# BUCK_5v_TPS54340_P-MOS.net
KiCad netlist of a schematic drawn in Altium Designer
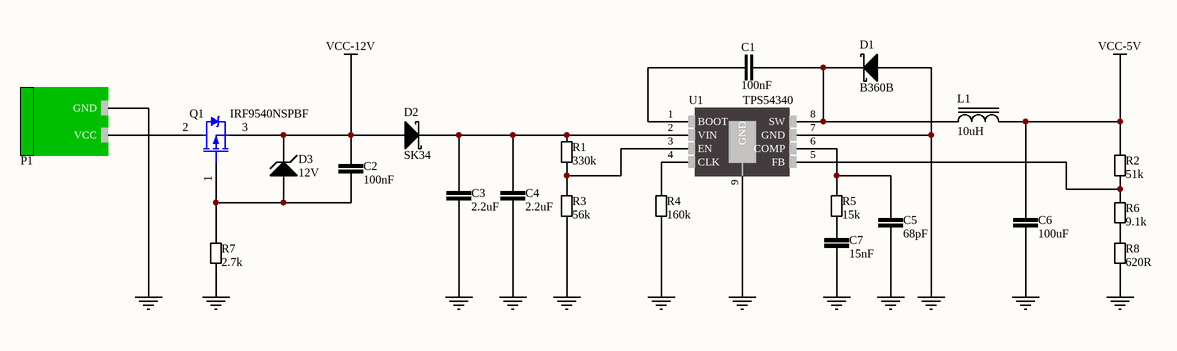
[diagram p0: BUCK_5v_TPS54340_P-MOS.SchDoc]

(export (version "E")
  (design (tool "Eeschema 10.0.6"))
  (components
    (comp (ref "C1")
      (value "100nF")
      (footprint "CER_0805")
      (description "CAP CER 100n 50V X7R 10% 0805")
      (libsource (lib "Capacitors") (part "00002105"))
    )
    (comp (ref "C2")
      (value "100nF")
      (footprint "CER_0805")
      (description "CAP CER 100n 50V X7R 10% 0805")
      (libsource (lib "Capacitors") (part "00002105"))
    )
    (comp (ref "C3")
      (value "2.2uF")
      (footprint "CER_1210")
      (description "CAP CER 2.2u")
      (libsource (lib "Capacitors") (part "00001225"))
    )
    (comp (ref "C4")
      (value "2.2uF")
      (footprint "CER_1210")
      (description "CAP CER 2.2u")
      (libsource (lib "Capacitors") (part "00001225"))
    )
    (comp (ref "C5")
      (value "68pF")
      (footprint "CER_0805")
      (description "CAP CER 100n 50V X7R 10% 0805")
      (libsource (lib "Capacitors") (part "00002105"))
    )
    (comp (ref "C6")
      (value "100uF")
      (footprint "CER_1210")
      (description "CAP CER 100u X5R 6.3V 10% 1210")
      (libsource (lib "Capacitors") (part "00002108"))
    )
    (comp (ref "C7")
      (value "15nF")
      (footprint "CER_0805")
      (description "CAP CER 100n 50V X7R 10% 0805")
      (libsource (lib "Capacitors") (part "00002105"))
    )
    (comp (ref "D1")
      (value "B360B")
      (footprint "DO214AC")
      (description "DIODE SCHOTTKY 60V 3A DO214AC")
      (fields (field (name "MANUFACTURER") "Vishay Semiconductor Diodes Division"))
      (libsource (lib "Discrete_Semiconductor") (part "B360B"))
    )
    (comp (ref "D2")
      (value "SK34")
      (footprint "DO214AC")
      (description "DIODE SCHOTTKY 40V 3A DO214AC")
      (fields (field (name "MANUFACTURER") "Vishay Semiconductor Diodes Division"))
      (libsource (lib "Discrete_Semiconductor") (part "SK34"))
    )
    (comp (ref "D3")
      (value "12V")
      (footprint "DO214AC")
      (description "DIODE ZENER")
      (fields
        (field (name "MANUFACTURER") "Vishay Semiconductor Diodes Division")
        (field (name "MANUFACTURER PART NUMBER") "B360B")
      )
      (libsource (lib "Discrete_Semiconductor") (part "ZENER"))
    )
    (comp (ref "L1")
      (value "10uH")
      (footprint "INDUCTOR_SS1260-103MLD")
      (description "FIXED IND 10uH 5.3A")
      (fields
        (field (name "MANUFACTURER") "Coilcraft")
        (field (name "MANUFACTURER PART NUMBER") "XAL7030-103MEB")
      )
      (libsource (lib "Discrete_Semiconductor") (part "Inductor_10uH"))
    )
    (comp (ref "P1")
      (value "2EDGRC-5.08-02P-14-00A(H)")
      (footprint "PWR_Con")
      (description "TERM BLOCK HDR 2POS 90DEG 5.08MM")
      (libsource (lib "Electro_Mechanical") (part "00000002"))
    )
    (comp (ref "Q1")
      (value "IRF9540NSPBF")
      (footprint "D2PAK-2")
      (description "P-MOS")
      (fields (field (name "MANUFACTURER") "INTERNATIONAL RECTIFIER"))
      (libsource (lib "Discrete_Semiconductor") (part "IRF9540N"))
    )
    (comp (ref "R1")
      (value "330k")
      (footprint "RESC2013X38N-0805-NOOVERLAY")
      (description "RES SMD 330 kOhm 1/8W 0805")
      (fields (field (name "POWER") "0.125W, 1/8W"))
      (libsource (lib "Resistors") (part "00003303"))
    )
    (comp (ref "R2")
      (value "51k")
      (footprint "RESC2013X38N-0805-NOOVERLAY")
      (description "RES SMD 51 kOhm 1/8W 0805")
      (fields (field (name "POWER") "0.125W, 1/8W"))
      (libsource (lib "Resistors") (part "00005102"))
    )
    (comp (ref "R3")
      (value "56k")
      (footprint "RESC2013X38N-0805-NOOVERLAY")
      (description "RES SMD 56 kOhm 1/8W 0805")
      (fields (field (name "POWER") "0.125W, 1/8W"))
      (libsource (lib "Resistors") (part "00005602"))
    )
    (comp (ref "R4")
      (value "160k")
      (footprint "RESC2013X38N-0805-NOOVERLAY")
      (description "RES SMD 160 kOhm 1/8W 0805")
      (fields (field (name "POWER") "0.125W, 1/8W"))
      (libsource (lib "Resistors") (part "00001603"))
    )
    (comp (ref "R5")
      (value "15k")
      (footprint "RESC2013X38N-0805-NOOVERLAY")
      (description "RES SMD 15 kOhm 1/8W 0805")
      (fields (field (name "POWER") "0.125W, 1/8W"))
      (libsource (lib "Resistors") (part "00001502"))
    )
    (comp (ref "R6")
      (value "9.1k")
      (footprint "RESC2013X38N-0805-NOOVERLAY")
      (description "RES SMD 9.1 kOhm 1/8W 0805")
      (fields (field (name "POWER") "0.125W, 1/8W"))
      (libsource (lib "Resistors") (part "00009101"))
    )
    (comp (ref "R7")
      (value "2.7k")
      (footprint "RESC2013X38N-0805-NOOVERLAY")
      (description "RES SMD 2.7 kOhm 1/8W 0805")
      (fields (field (name "POWER") "0.125W, 1/8W"))
      (libsource (lib "Resistors") (part "00002701"))
    )
    (comp (ref "R8")
      (value "620R")
      (footprint "RESC2013X38N-0805-NOOVERLAY")
      (description "RES SMD 620 Ohm 1/8W 0805")
      (fields (field (name "POWER") "0.125W, 1/8W"))
      (libsource (lib "Resistors") (part "00006200"))
    )
    (comp (ref "U1")
      (value "TPS54340")
      (footprint "HSOP-8")
      (description "IC REG BUCK ADJ 3.5A 8SOPWRPAD")
      (libsource (lib "Integrated_circuits") (part "TPS54340"))
    )
  )
  (nets
    (net (code "1") (name "GND") (class "Default")
      (node (ref "C3") (pin "1") (pinfunction "1_1") (pintype "passive"))
      (node (ref "C4") (pin "1") (pinfunction "1_1") (pintype "passive"))
      (node (ref "C5") (pin "1") (pinfunction "1_1") (pintype "passive"))
      (node (ref "C6") (pin "1") (pinfunction "1_1") (pintype "passive"))
      (node (ref "C7") (pin "1") (pinfunction "1_1") (pintype "passive"))
      (node (ref "D1") (pin "2") (pinfunction "Anode_2") (pintype "passive"))
      (node (ref "P1") (pin "1") (pinfunction "GND_1") (pintype "passive"))
      (node (ref "R3") (pin "1") (pinfunction "1_1") (pintype "passive"))
      (node (ref "R4") (pin "1") (pinfunction "1_1") (pintype "passive"))
      (node (ref "R7") (pin "1") (pinfunction "1_1") (pintype "passive"))
      (node (ref "R8") (pin "1") (pinfunction "1_1") (pintype "passive"))
      (node (ref "U1") (pin "7") (pinfunction "GND_7") (pintype "passive"))
      (node (ref "U1") (pin "9") (pinfunction "GND_9") (pintype "passive"))
    )
    (net (code "2") (name "Net-(C7-Pad2)") (class "Default")
      (node (ref "C7") (pin "2") (pinfunction "2_2") (pintype "passive"))
      (node (ref "R5") (pin "1") (pinfunction "1_1") (pintype "passive"))
    )
    (net (code "3") (name "Net-(D1-Cathode)") (class "Default")
      (node (ref "C1") (pin "2") (pinfunction "2_2") (pintype "passive"))
      (node (ref "D1") (pin "1") (pinfunction "Cathode_1") (pintype "passive"))
      (node (ref "L1") (pin "1") (pinfunction "1_1") (pintype "passive"))
      (node (ref "U1") (pin "8") (pinfunction "SW_8") (pintype "passive"))
    )
    (net (code "4") (name "Net-(D2-Cathode)") (class "Default")
      (node (ref "C3") (pin "2") (pinfunction "2_2") (pintype "passive"))
      (node (ref "C4") (pin "2") (pinfunction "2_2") (pintype "passive"))
      (node (ref "D2") (pin "1") (pinfunction "Cathode_1") (pintype "passive"))
      (node (ref "R1") (pin "2") (pinfunction "2_2") (pintype "passive"))
      (node (ref "U1") (pin "2") (pinfunction "VIN_2") (pintype "passive"))
    )
    (net (code "5") (name "Net-(D3-Anode)") (class "Default")
      (node (ref "C2") (pin "1") (pinfunction "1_1") (pintype "passive"))
      (node (ref "D3") (pin "2") (pinfunction "Anode_2") (pintype "passive"))
      (node (ref "Q1") (pin "1") (pinfunction "G_1") (pintype "passive"))
      (node (ref "R7") (pin "2") (pinfunction "2_2") (pintype "passive"))
    )
    (net (code "6") (name "Net-(P1-VCC)") (class "Default")
      (node (ref "P1") (pin "2") (pinfunction "VCC_2") (pintype "passive"))
      (node (ref "Q1") (pin "2") (pinfunction "D_2") (pintype "passive"))
    )
    (net (code "7") (name "Net-(R6-Pad1)") (class "Default")
      (node (ref "R6") (pin "1") (pinfunction "1_1") (pintype "passive"))
      (node (ref "R8") (pin "2") (pinfunction "2_2") (pintype "passive"))
    )
    (net (code "8") (name "Net-(U1-BOOT)") (class "Default")
      (node (ref "C1") (pin "1") (pinfunction "1_1") (pintype "passive"))
      (node (ref "U1") (pin "1") (pinfunction "BOOT_1") (pintype "passive"))
    )
    (net (code "9") (name "Net-(U1-CLK)") (class "Default")
      (node (ref "R4") (pin "2") (pinfunction "2_2") (pintype "passive"))
      (node (ref "U1") (pin "4") (pinfunction "CLK_4") (pintype "passive"))
    )
    (net (code "10") (name "Net-(U1-COMP)") (class "Default")
      (node (ref "C5") (pin "2") (pinfunction "2_2") (pintype "passive"))
      (node (ref "R5") (pin "2") (pinfunction "2_2") (pintype "passive"))
      (node (ref "U1") (pin "6") (pinfunction "COMP_6") (pintype "passive"))
    )
    (net (code "11") (name "Net-(U1-EN)") (class "Default")
      (node (ref "R1") (pin "1") (pinfunction "1_1") (pintype "passive"))
      (node (ref "R3") (pin "2") (pinfunction "2_2") (pintype "passive"))
      (node (ref "U1") (pin "3") (pinfunction "EN_3") (pintype "passive"))
    )
    (net (code "12") (name "Net-(U1-FB)") (class "Default")
      (node (ref "R2") (pin "1") (pinfunction "1_1") (pintype "passive"))
      (node (ref "R6") (pin "2") (pinfunction "2_2") (pintype "passive"))
      (node (ref "U1") (pin "5") (pinfunction "FB_5") (pintype "passive"))
    )
    (net (code "13") (name "VCC-5V") (class "Default")
      (node (ref "C6") (pin "2") (pinfunction "2_2") (pintype "passive"))
      (node (ref "L1") (pin "2") (pinfunction "2_2") (pintype "passive"))
      (node (ref "R2") (pin "2") (pinfunction "2_2") (pintype "passive"))
    )
    (net (code "14") (name "VCC-12V") (class "Default")
      (node (ref "C2") (pin "2") (pinfunction "2_2") (pintype "passive"))
      (node (ref "D2") (pin "2") (pinfunction "Anode_2") (pintype "passive"))
      (node (ref "D3") (pin "1") (pinfunction "Cathode_1") (pintype "passive"))
      (node (ref "Q1") (pin "3") (pinfunction "S_3") (pintype "passive"))
    )
  )
)
